# 1-Schematic_syntheseproject_planA_ok.net
KiCad netlist of a schematic drawn in EasyEDA
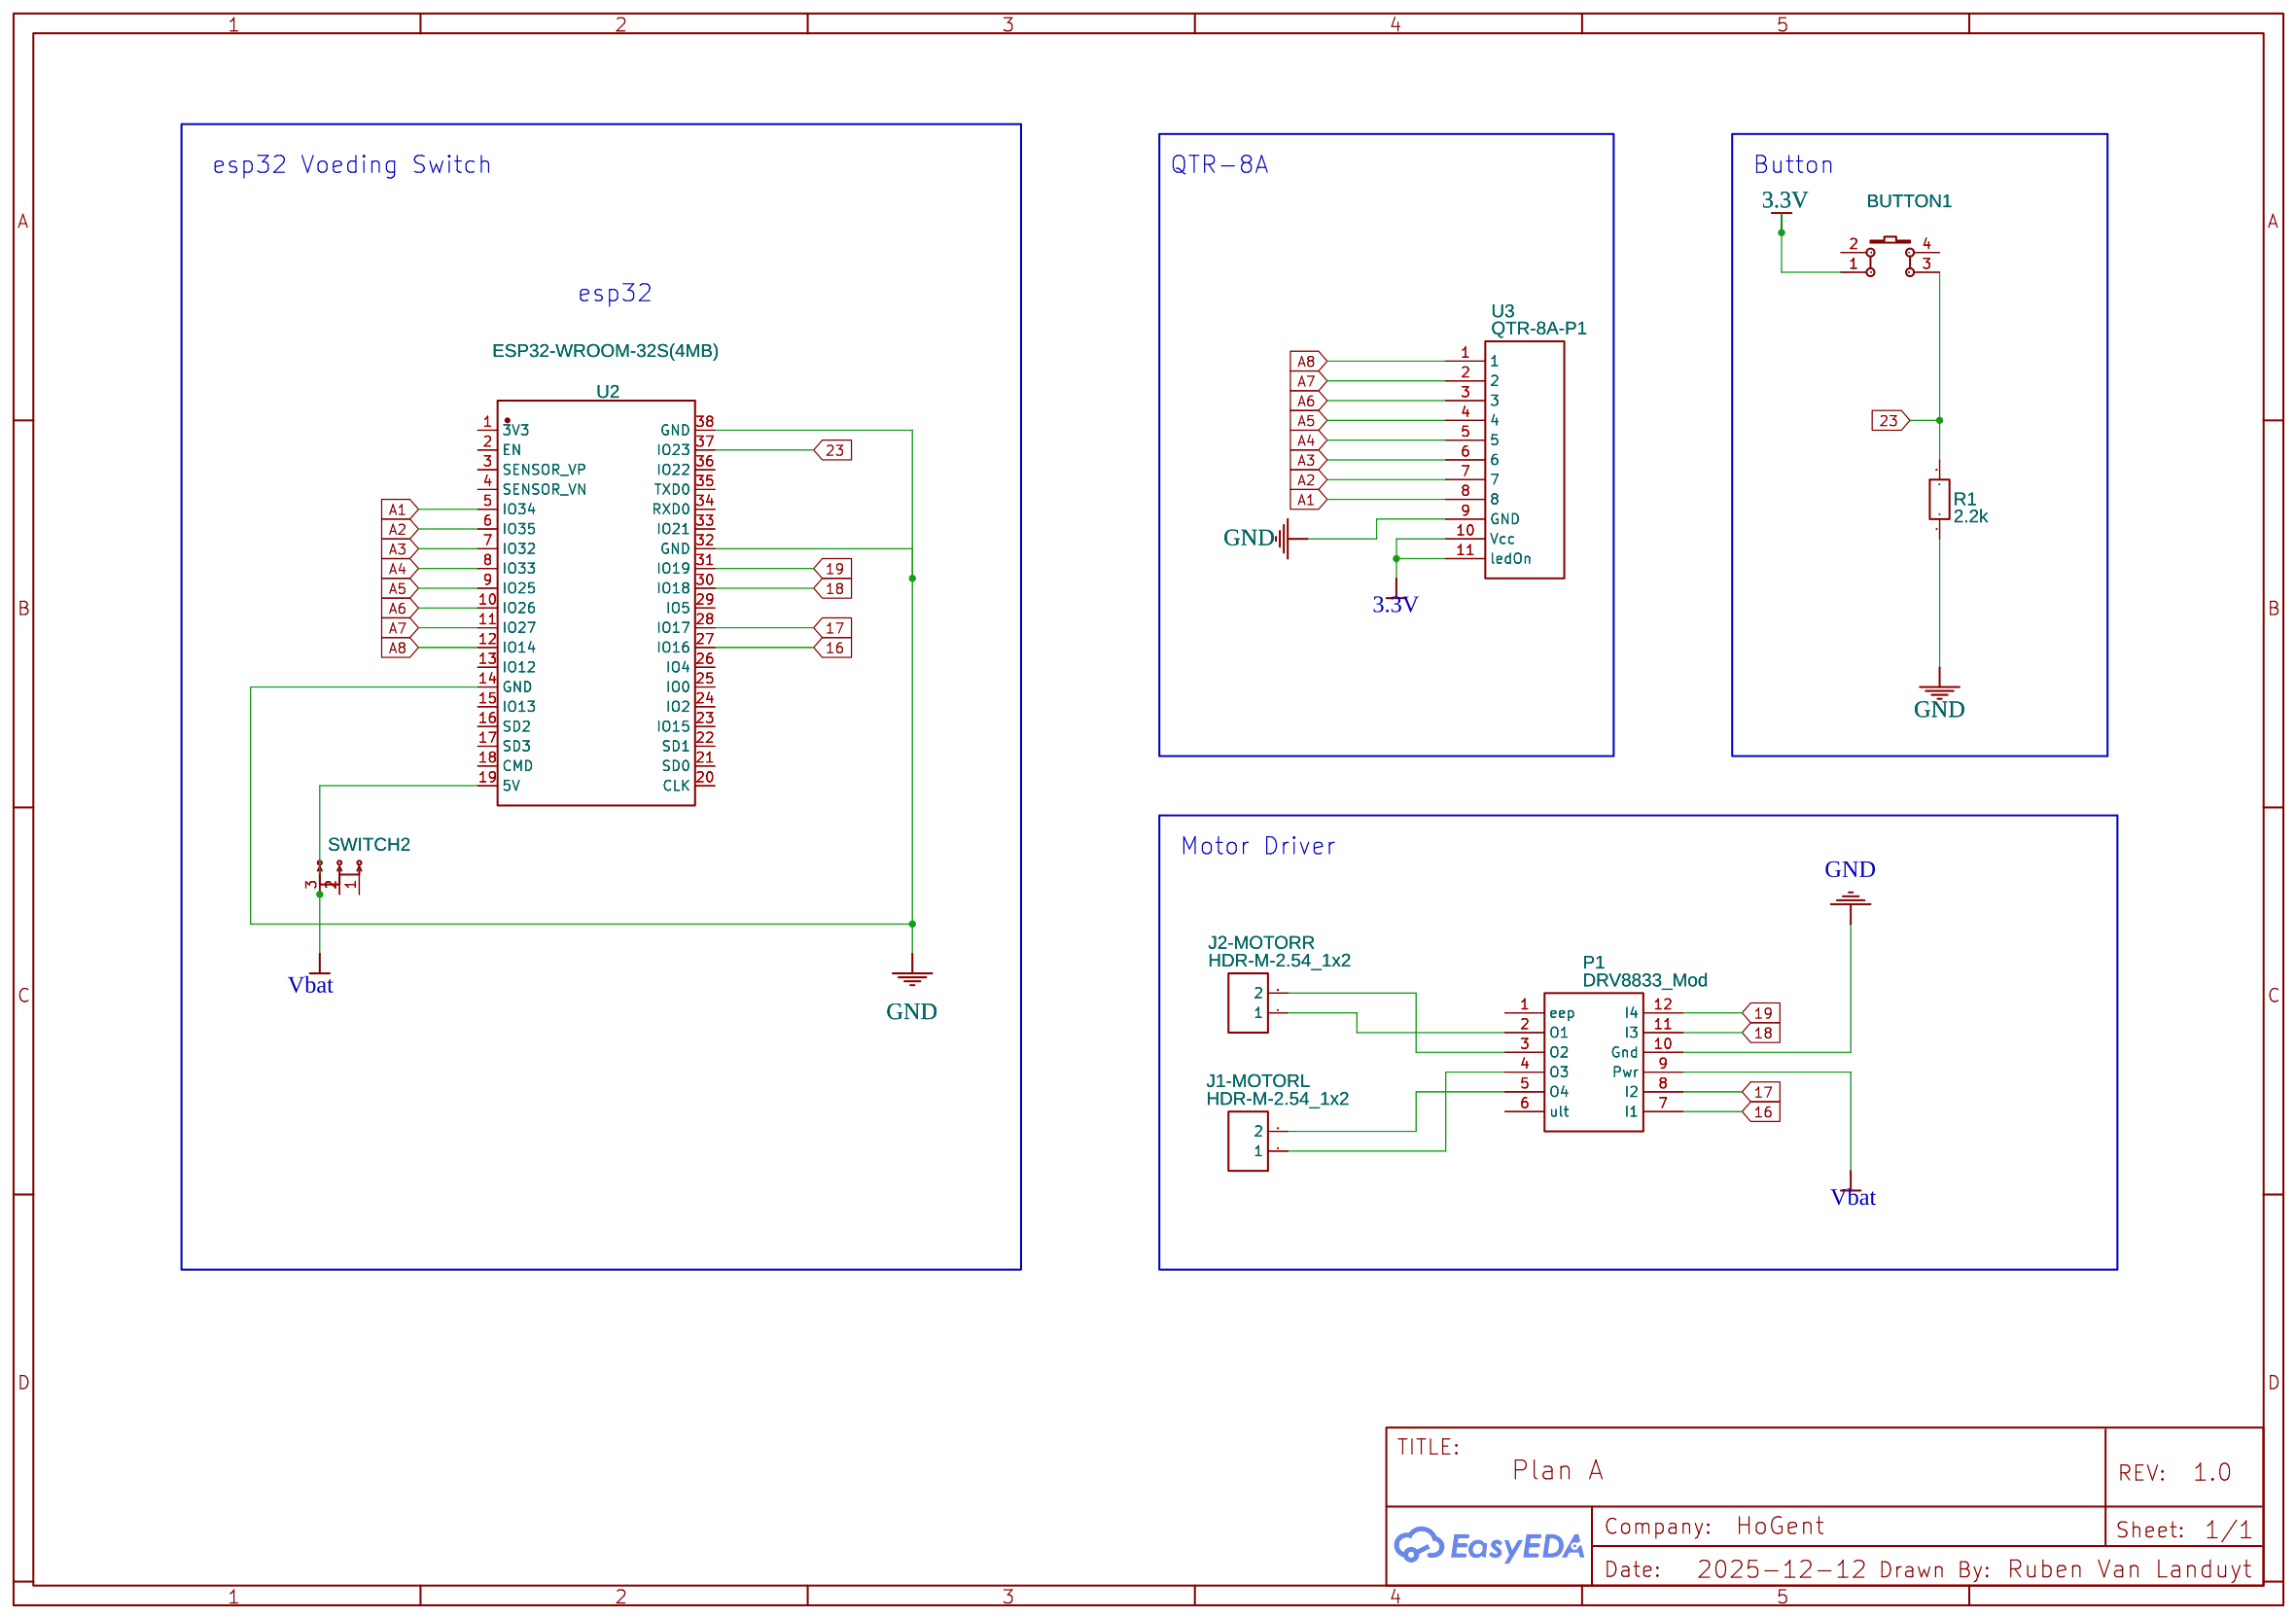
[diagram p0: schematic sheet]

(export (version "E")
  (design (tool "Eeschema 10.0.6"))
  (components
    (comp (ref "BUTTON1")
      (value "K4-6×6_SMD")
      (fields (field (name "Manufacturer Part") "K2-6639SP-D4SC-04") (field (name "Manufacturer") "韩国韩荣"))
      (libsource (lib "") (part "K4-6×6_SMD"))
    )
    (comp (ref "J1-MOTORL") (value "HDR-M-2.54_1x2") (libsource (lib "") (part "HDR-M-2.54_1x2")))
    (comp (ref "J2-MOTORR") (value "HDR-M-2.54_1x2") (libsource (lib "") (part "HDR-M-2.54_1x2_1")))
    (comp (ref "P1") (value "DRV8833_Mod") (libsource (lib "") (part "DRV8833_Mod")))
    (comp (ref "R1") (value "2.2k") (libsource (lib "") (part "R_0805_EU")))
    (comp (ref "SWITCH2")
      (value "SS12D00G3_C50377147")
      (fields (field (name "Manufacturer Part") "SS12D00G3") (field (name "Manufacturer") "YIZHI(逸致)"))
      (libsource (lib "") (part "SS12D00G3_C50377147"))
    )
    (comp (ref "U2")
      (value "ESP32-WROOM-32S(4MB)")
      (fields (field (name "Manufacturer") "Espressif Systems"))
      (libsource (lib "") (part "ESP32-WROOM-32S(4MB)"))
    )
    (comp (ref "U3") (value "QTR-8A-P1") (libsource (lib "") (part "QTR-8A-P1")))
  )
  (nets
    (net (code "1") (name "3.3V") (class "Default")
      (node (ref "BUTTON1") (pin "1") (pinfunction "1_1") (pintype "unspecified"))
      (node (ref "U3") (pin "10") (pinfunction "Vcc_10") (pintype "unspecified"))
      (node (ref "U3") (pin "11") (pinfunction "ledOn_11") (pintype "unspecified"))
    )
    (net (code "2") (name "16") (class "Default")
      (node (ref "P1") (pin "7") (pinfunction "I1_7") (pintype "unspecified"))
      (node (ref "U2") (pin "27") (pinfunction "IO16_27") (pintype "unspecified"))
    )
    (net (code "3") (name "17") (class "Default")
      (node (ref "P1") (pin "8") (pinfunction "I2_8") (pintype "unspecified"))
      (node (ref "U2") (pin "28") (pinfunction "IO17_28") (pintype "unspecified"))
    )
    (net (code "4") (name "18") (class "Default")
      (node (ref "P1") (pin "11") (pinfunction "I3_11") (pintype "unspecified"))
      (node (ref "U2") (pin "30") (pinfunction "IO18_30") (pintype "unspecified"))
    )
    (net (code "5") (name "19") (class "Default")
      (node (ref "P1") (pin "12") (pinfunction "I4_12") (pintype "unspecified"))
      (node (ref "U2") (pin "31") (pinfunction "IO19_31") (pintype "unspecified"))
    )
    (net (code "6") (name "23") (class "Default")
      (node (ref "BUTTON1") (pin "3") (pinfunction "3_3") (pintype "unspecified"))
      (node (ref "R1") (pin "2") (pinfunction "2_2") (pintype "unspecified"))
      (node (ref "U2") (pin "37") (pinfunction "IO23_37") (pintype "unspecified"))
    )
    (net (code "7") (name "A1") (class "Default")
      (node (ref "U2") (pin "5") (pinfunction "IO34_5") (pintype "unspecified"))
      (node (ref "U3") (pin "8") (pinfunction "8_8") (pintype "unspecified"))
    )
    (net (code "8") (name "A2") (class "Default")
      (node (ref "U2") (pin "6") (pinfunction "IO35_6") (pintype "unspecified"))
      (node (ref "U3") (pin "7") (pinfunction "7_7") (pintype "unspecified"))
    )
    (net (code "9") (name "A3") (class "Default")
      (node (ref "U2") (pin "7") (pinfunction "IO32_7") (pintype "unspecified"))
      (node (ref "U3") (pin "6") (pinfunction "6_6") (pintype "unspecified"))
    )
    (net (code "10") (name "A4") (class "Default")
      (node (ref "U2") (pin "8") (pinfunction "IO33_8") (pintype "unspecified"))
      (node (ref "U3") (pin "5") (pinfunction "5_5") (pintype "unspecified"))
    )
    (net (code "11") (name "A5") (class "Default")
      (node (ref "U2") (pin "9") (pinfunction "IO25_9") (pintype "unspecified"))
      (node (ref "U3") (pin "4") (pinfunction "4_4") (pintype "unspecified"))
    )
    (net (code "12") (name "A6") (class "Default")
      (node (ref "U2") (pin "10") (pinfunction "IO26_10") (pintype "unspecified"))
      (node (ref "U3") (pin "3") (pinfunction "3_3") (pintype "unspecified"))
    )
    (net (code "13") (name "A7") (class "Default")
      (node (ref "U2") (pin "11") (pinfunction "IO27_11") (pintype "unspecified"))
      (node (ref "U3") (pin "2") (pinfunction "2_2") (pintype "unspecified"))
    )
    (net (code "14") (name "A8") (class "Default")
      (node (ref "U2") (pin "12") (pinfunction "IO14_12") (pintype "unspecified"))
      (node (ref "U3") (pin "1") (pinfunction "1_1") (pintype "unspecified"))
    )
    (net (code "15") (name "GND") (class "Default")
      (node (ref "P1") (pin "10") (pinfunction "Gnd_10") (pintype "unspecified"))
      (node (ref "R1") (pin "1") (pinfunction "1_1") (pintype "unspecified"))
      (node (ref "U2") (pin "14") (pinfunction "GND_14") (pintype "unspecified"))
      (node (ref "U2") (pin "32") (pinfunction "GND_32") (pintype "unspecified"))
      (node (ref "U2") (pin "38") (pinfunction "GND_38") (pintype "unspecified"))
      (node (ref "U3") (pin "9") (pinfunction "GND_9") (pintype "unspecified"))
    )
    (net (code "16") (name "Net-(P1-O1)") (class "Default")
      (node (ref "J2-MOTORR") (pin "1") (pinfunction "1_1") (pintype "unspecified"))
      (node (ref "P1") (pin "2") (pinfunction "O1_2") (pintype "unspecified"))
    )
    (net (code "17") (name "Net-(P1-O2)") (class "Default")
      (node (ref "J2-MOTORR") (pin "2") (pinfunction "2_2") (pintype "unspecified"))
      (node (ref "P1") (pin "3") (pinfunction "O2_3") (pintype "unspecified"))
    )
    (net (code "18") (name "Net-(P1-O3)") (class "Default")
      (node (ref "J1-MOTORL") (pin "1") (pinfunction "1_1") (pintype "unspecified"))
      (node (ref "P1") (pin "4") (pinfunction "O3_4") (pintype "unspecified"))
    )
    (net (code "19") (name "Net-(P1-O4)") (class "Default")
      (node (ref "J1-MOTORL") (pin "2") (pinfunction "2_2") (pintype "unspecified"))
      (node (ref "P1") (pin "5") (pinfunction "O4_5") (pintype "unspecified"))
    )
    (net (code "20") (name "Vbat") (class "Default")
      (node (ref "P1") (pin "9") (pinfunction "Pwr_9") (pintype "unspecified"))
      (node (ref "SWITCH2") (pin "3") (pinfunction "3_3") (pintype "unspecified"))
      (node (ref "U2") (pin "19") (pinfunction "5V_19") (pintype "unspecified"))
    )
    (net (code "21") (name "unconnected-(BUTTON1-Pad2)") (class "Default")
      (node (ref "BUTTON1") (pin "2") (pinfunction "2_2") (pintype "unspecified"))
    )
    (net (code "22") (name "unconnected-(BUTTON1-Pad4)") (class "Default")
      (node (ref "BUTTON1") (pin "4") (pinfunction "4_4") (pintype "unspecified"))
    )
    (net (code "23") (name "unconnected-(P1-eep-Pad1)") (class "Default")
      (node (ref "P1") (pin "1") (pinfunction "eep_1") (pintype "unspecified"))
    )
    (net (code "24") (name "unconnected-(P1-ult-Pad6)") (class "Default")
      (node (ref "P1") (pin "6") (pinfunction "ult_6") (pintype "unspecified"))
    )
    (net (code "25") (name "unconnected-(SWITCH2-Pad1)") (class "Default")
      (node (ref "SWITCH2") (pin "1") (pinfunction "1_1") (pintype "unspecified"))
    )
    (net (code "26") (name "unconnected-(SWITCH2-Pad2)") (class "Default")
      (node (ref "SWITCH2") (pin "2") (pinfunction "2_2") (pintype "unspecified"))
    )
    (net (code "27") (name "unconnected-(U2-3V3-Pad1)") (class "Default")
      (node (ref "U2") (pin "1") (pinfunction "3V3_1") (pintype "unspecified"))
    )
    (net (code "28") (name "unconnected-(U2-CLK-Pad20)") (class "Default")
      (node (ref "U2") (pin "20") (pinfunction "CLK_20") (pintype "unspecified"))
    )
    (net (code "29") (name "unconnected-(U2-CMD-Pad18)") (class "Default")
      (node (ref "U2") (pin "18") (pinfunction "CMD_18") (pintype "unspecified"))
    )
    (net (code "30") (name "unconnected-(U2-EN-Pad2)") (class "Default")
      (node (ref "U2") (pin "2") (pinfunction "EN_2") (pintype "unspecified"))
    )
    (net (code "31") (name "unconnected-(U2-IO0-Pad25)") (class "Default")
      (node (ref "U2") (pin "25") (pinfunction "IO0_25") (pintype "unspecified"))
    )
    (net (code "32") (name "unconnected-(U2-IO2-Pad24)") (class "Default")
      (node (ref "U2") (pin "24") (pinfunction "IO2_24") (pintype "unspecified"))
    )
    (net (code "33") (name "unconnected-(U2-IO4-Pad26)") (class "Default")
      (node (ref "U2") (pin "26") (pinfunction "IO4_26") (pintype "unspecified"))
    )
    (net (code "34") (name "unconnected-(U2-IO5-Pad29)") (class "Default")
      (node (ref "U2") (pin "29") (pinfunction "IO5_29") (pintype "unspecified"))
    )
    (net (code "35") (name "unconnected-(U2-IO12-Pad13)") (class "Default")
      (node (ref "U2") (pin "13") (pinfunction "IO12_13") (pintype "unspecified"))
    )
    (net (code "36") (name "unconnected-(U2-IO13-Pad15)") (class "Default")
      (node (ref "U2") (pin "15") (pinfunction "IO13_15") (pintype "unspecified"))
    )
    (net (code "37") (name "unconnected-(U2-IO15-Pad23)") (class "Default")
      (node (ref "U2") (pin "23") (pinfunction "IO15_23") (pintype "unspecified"))
    )
    (net (code "38") (name "unconnected-(U2-IO21-Pad33)") (class "Default")
      (node (ref "U2") (pin "33") (pinfunction "IO21_33") (pintype "unspecified"))
    )
    (net (code "39") (name "unconnected-(U2-IO22-Pad36)") (class "Default")
      (node (ref "U2") (pin "36") (pinfunction "IO22_36") (pintype "unspecified"))
    )
    (net (code "40") (name "unconnected-(U2-RXD0-Pad34)") (class "Default")
      (node (ref "U2") (pin "34") (pinfunction "RXD0_34") (pintype "unspecified"))
    )
    (net (code "41") (name "unconnected-(U2-SD0-Pad21)") (class "Default")
      (node (ref "U2") (pin "21") (pinfunction "SD0_21") (pintype "unspecified"))
    )
    (net (code "42") (name "unconnected-(U2-SD1-Pad22)") (class "Default")
      (node (ref "U2") (pin "22") (pinfunction "SD1_22") (pintype "unspecified"))
    )
    (net (code "43") (name "unconnected-(U2-SD2-Pad16)") (class "Default")
      (node (ref "U2") (pin "16") (pinfunction "SD2_16") (pintype "unspecified"))
    )
    (net (code "44") (name "unconnected-(U2-SD3-Pad17)") (class "Default")
      (node (ref "U2") (pin "17") (pinfunction "SD3_17") (pintype "unspecified"))
    )
    (net (code "45") (name "unconnected-(U2-SENSOR_VN-Pad4)") (class "Default")
      (node (ref "U2") (pin "4") (pinfunction "SENSOR_VN_4") (pintype "unspecified"))
    )
    (net (code "46") (name "unconnected-(U2-SENSOR_VP-Pad3)") (class "Default")
      (node (ref "U2") (pin "3") (pinfunction "SENSOR_VP_3") (pintype "unspecified"))
    )
    (net (code "47") (name "unconnected-(U2-TXD0-Pad35)") (class "Default")
      (node (ref "U2") (pin "35") (pinfunction "TXD0_35") (pintype "unspecified"))
    )
  )
)
